# PCB_1c.net
KiCad netlist of a schematic drawn in EAGLE
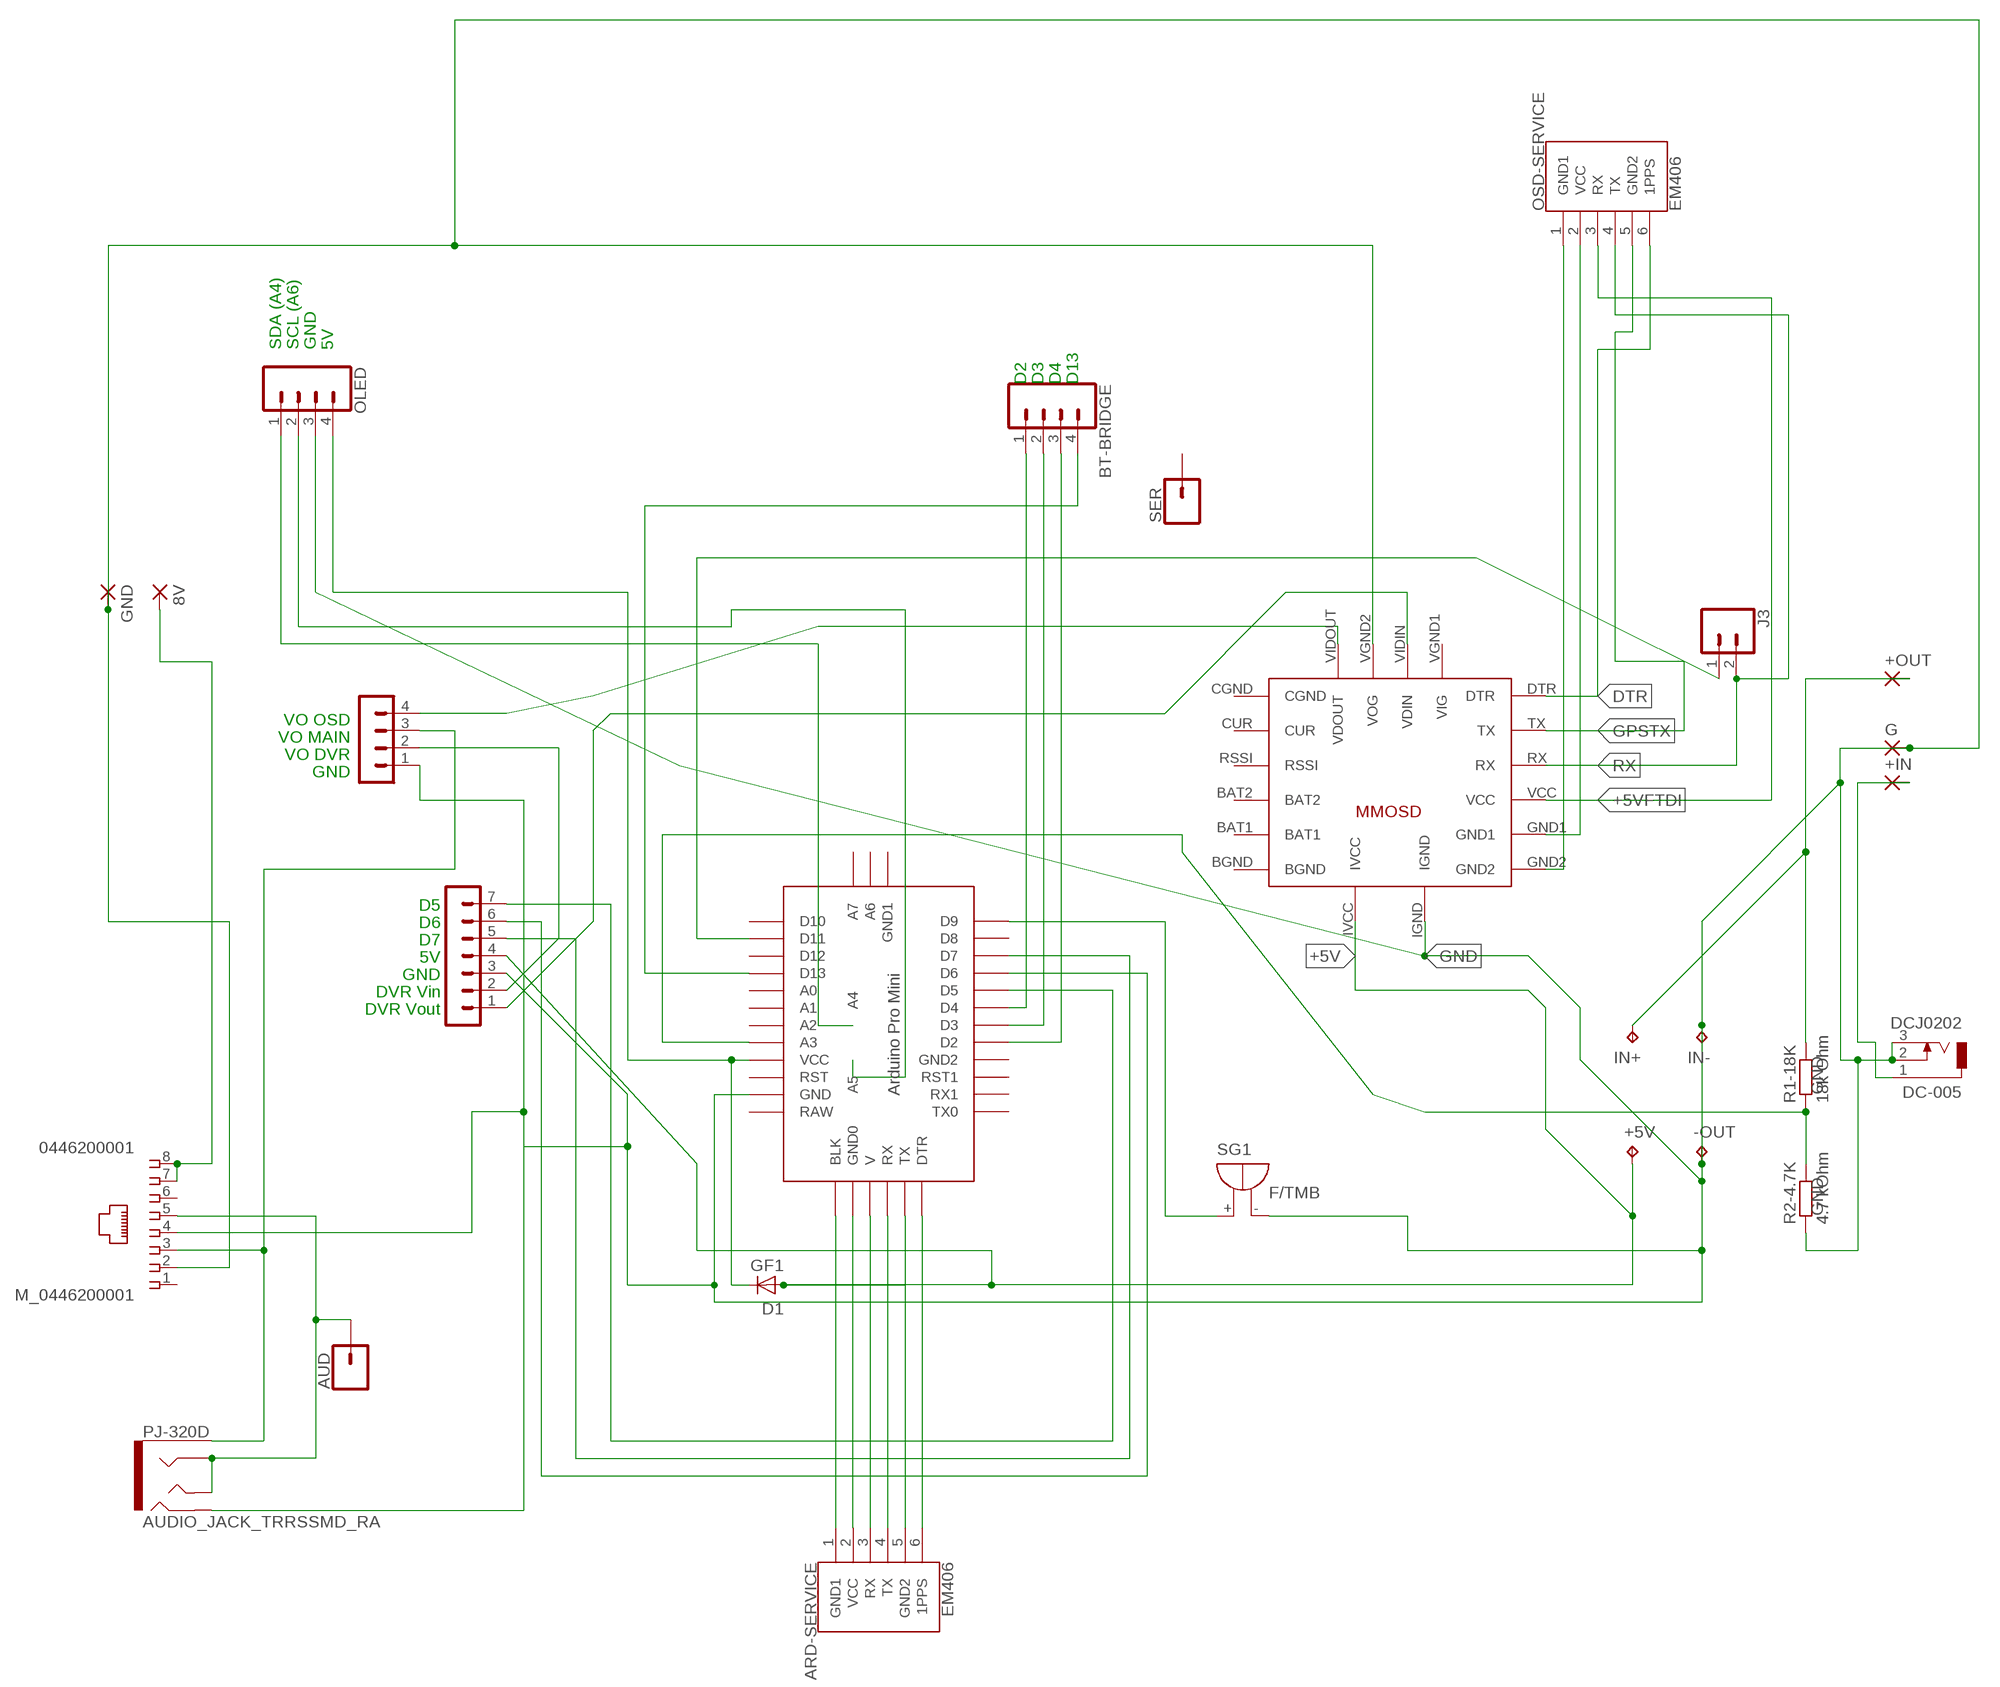
[diagram p0: schematic, sheet 1]

(export (version "E")
  (design (tool "Eeschema 10.0.6"))
  (components
    (comp (ref "+5V")
      (value "TPTP20SQ")
      (footprint "eagle-import:TP20SQ")
      (libsource (lib "eagle-import") (part "TPTP20SQ"))
    )
    (comp (ref "+IN")
      (value "2,54/1,1")
      (footprint "eagle-import:2,54_1,1")
      (libsource (lib "eagle-import") (part "2,54/1,1"))
    )
    (comp (ref "+OUT")
      (value "2,54/1,1")
      (footprint "eagle-import:2,54_1,1")
      (libsource (lib "eagle-import") (part "2,54/1,1"))
    )
    (comp (ref "-OUT")
      (value "TPTP20SQ")
      (footprint "eagle-import:TP20SQ")
      (libsource (lib "eagle-import") (part "TPTP20SQ"))
    )
    (comp (ref "8V")
      (value "2,54/1,1")
      (footprint "eagle-import:2,54_1,1")
      (libsource (lib "eagle-import") (part "2,54/1,1"))
    )
    (comp (ref "ARD-SERVICE")
      (value "EM406")
      (footprint "eagle-import:1X06-1MM")
      (libsource (lib "eagle-import") (part "EM406"))
    )
    (comp (ref "AUD")
      (value "CONN_01")
      (footprint "eagle-import:1X01")
      (libsource (lib "eagle-import") (part "CONN_01"))
    )
    (comp (ref "BT-BRIDGE")
      (value "CONN_04")
      (footprint "eagle-import:1X04")
      (libsource (lib "eagle-import") (part "CONN_04"))
    )
    (comp (ref "D1")
      (value "GF1")
      (footprint "eagle-import:SMA-DO214AC")
      (libsource (lib "eagle-import") (part "GF1"))
    )
    (comp (ref "DC-005")
      (value "DCJ0202")
      (footprint "eagle-import:DCJ0202")
      (libsource (lib "eagle-import") (part "DCJ0202"))
    )
    (comp (ref "DVR/MODULE-IO")
      (value "MA07-1")
      (footprint "eagle-import:MA07-1")
      (libsource (lib "eagle-import") (part "MA07-1"))
    )
    (comp (ref "G")
      (value "2,54/1,1")
      (footprint "eagle-import:2,54_1,1")
      (libsource (lib "eagle-import") (part "2,54/1,1"))
    )
    (comp (ref "GND")
      (value "2,54/1,1")
      (footprint "eagle-import:2,54_1,1")
      (libsource (lib "eagle-import") (part "2,54/1,1"))
    )
    (comp (ref "IN+")
      (value "TPTP20SQ")
      (footprint "eagle-import:TP20SQ")
      (libsource (lib "eagle-import") (part "TPTP20SQ"))
    )
    (comp (ref "IN-")
      (value "TPTP20SQ")
      (footprint "eagle-import:TP20SQ")
      (libsource (lib "eagle-import") (part "TPTP20SQ"))
    )
    (comp (ref "J3")
      (value "CONN_02")
      (footprint "eagle-import:1X02")
      (libsource (lib "eagle-import") (part "CONN_02"))
    )
    (comp (ref "MINIMOSD")
      (value "MICROMINIMOSDPWR")
      (footprint "eagle-import:MMOSDNVDVID")
      (libsource (lib "eagle-import") (part "MICROMINIMOSDPWR"))
    )
    (comp (ref "M_0446200001")
      (value "0446200001")
      (footprint "eagle-import:0446200001")
      (fields (field (name "MF") "MOLEX"))
      (libsource (lib "eagle-import") (part "0446200001"))
    )
    (comp (ref "OLED")
      (value "CONN_04")
      (footprint "eagle-import:1X04")
      (libsource (lib "eagle-import") (part "CONN_04"))
    )
    (comp (ref "OSD-SERVICE")
      (value "EM406")
      (footprint "eagle-import:1X06-1MM")
      (libsource (lib "eagle-import") (part "EM406"))
    )
    (comp (ref "PJ-320D")
      (value "AUDIO_JACK_TRRSSMD_RA")
      (footprint "eagle-import:AUDIO_JACK_3.5MM_TRRS_SMD_RA")
      (libsource (lib "eagle-import") (part "AUDIO_JACK_TRRSSMD_RA"))
    )
    (comp (ref "R1-18K")
      (value "18k Ohm")
      (footprint "eagle-import:M1206")
      (libsource (lib "eagle-import") (part "R-EU_M1206"))
    )
    (comp (ref "R2-4.7K")
      (value "4.7 kOhm")
      (footprint "eagle-import:M1206")
      (libsource (lib "eagle-import") (part "R-EU_M1206"))
    )
    (comp (ref "SER")
      (value "CONN_01")
      (footprint "eagle-import:1X01")
      (libsource (lib "eagle-import") (part "CONN_01"))
    )
    (comp (ref "SG1")
      (value "F/TMB")
      (footprint "eagle-import:F_TMB")
      (libsource (lib "eagle-import") (part "F/TMB"))
    )
    (comp (ref "U$1")
      (value "ABK-PRO-MINI")
      (footprint "eagle-import:ABK-PRO-MINI")
      (libsource (lib "eagle-import") (part "ABK-PRO-MINI"))
    )
    (comp (ref "V-IO")
      (value "MA04-1")
      (footprint "eagle-import:MA04-1")
      (libsource (lib "eagle-import") (part "MA04-1"))
    )
  )
  (nets
    (net (code "1") (name "+5V") (class "Default")
      (node (ref "+5V") (pin "TP") (pinfunction "TP_TP") (pintype "input"))
      (node (ref "D1") (pin "A") (pinfunction "A_A") (pintype "passive"))
      (node (ref "DVR/MODULE-IO") (pin "4") (pinfunction "4_4") (pintype "passive"))
      (node (ref "MINIMOSD") (pin "IVCC") (pinfunction "IVCC_IVCC") (pintype "power_in"))
    )
    (net (code "2") (name "+5VFTDI") (class "Default")
      (node (ref "MINIMOSD") (pin "VCC") (pinfunction "VCC_VCC") (pintype "power_in"))
      (node (ref "OSD-SERVICE") (pin "3") (pinfunction "RX_3") (pintype "bidirectional"))
    )
    (net (code "3") (name "/BAT1") (class "Default")
      (node (ref "MINIMOSD") (pin "BAT1") (pinfunction "BAT1_BAT1") (pintype "power_in"))
    )
    (net (code "4") (name "/BAT2") (class "Default")
      (node (ref "MINIMOSD") (pin "BAT2") (pinfunction "BAT2_BAT2") (pintype "power_in"))
    )
    (net (code "5") (name "/BGND") (class "Default")
      (node (ref "MINIMOSD") (pin "BGND") (pinfunction "BGND_BGND") (pintype "power_in"))
    )
    (net (code "6") (name "/CGND") (class "Default")
      (node (ref "MINIMOSD") (pin "CGND") (pinfunction "CGND_CGND") (pintype "power_in"))
    )
    (net (code "7") (name "DTR") (class "Default")
      (node (ref "MINIMOSD") (pin "DTR") (pinfunction "DTR_DTR") (pintype "bidirectional"))
      (node (ref "OSD-SERVICE") (pin "6") (pinfunction "1PPS_6") (pintype "bidirectional"))
    )
    (net (code "8") (name "GND") (class "Default")
      (node (ref "-OUT") (pin "TP") (pinfunction "TP_TP") (pintype "input"))
      (node (ref "DC-005") (pin "2") (pinfunction "2_2") (pintype "passive"))
      (node (ref "DC-005") (pin "3") (pinfunction "3_3") (pintype "passive"))
      (node (ref "DVR/MODULE-IO") (pin "3") (pinfunction "3_3") (pintype "passive"))
      (node (ref "G") (pin "1") (pinfunction "P_1") (pintype "passive"))
      (node (ref "GND") (pin "1") (pinfunction "P_1") (pintype "passive"))
      (node (ref "IN-") (pin "TP") (pinfunction "TP_TP") (pintype "input"))
      (node (ref "MINIMOSD") (pin "IGND") (pinfunction "IGND_IGND") (pintype "power_in"))
      (node (ref "MINIMOSD") (pin "VGND2") (pinfunction "VOG_VGND2") (pintype "output"))
      (node (ref "M_0446200001") (pin "2") (pinfunction "2_2") (pintype "passive"))
      (node (ref "M_0446200001") (pin "4") (pinfunction "4_4") (pintype "passive"))
      (node (ref "OLED") (pin "3") (pinfunction "3_3") (pintype "passive"))
      (node (ref "PJ-320D") (pin "RING2") (pinfunction "RING2_RING2") (pintype "bidirectional"))
      (node (ref "R2-4.7K") (pin "1") (pinfunction "1_1") (pintype "passive"))
      (node (ref "SG1") (pin "-") (pinfunction "-_-") (pintype "passive"))
      (node (ref "U$1") (pin "GND") (pinfunction "GND_GND") (pintype "bidirectional"))
      (node (ref "V-IO") (pin "1") (pinfunction "1_1") (pintype "passive"))
    )
    (net (code "9") (name "GPSTX") (class "Default")
      (node (ref "MINIMOSD") (pin "TX") (pinfunction "TX_TX") (pintype "output"))
      (node (ref "OSD-SERVICE") (pin "5") (pinfunction "GND2_5") (pintype "bidirectional"))
    )
    (net (code "10") (name "Net-(+IN-P)") (class "Default")
      (node (ref "+IN") (pin "1") (pinfunction "P_1") (pintype "passive"))
      (node (ref "DC-005") (pin "1") (pinfunction "1_1") (pintype "passive"))
    )
    (net (code "11") (name "Net-(+OUT-P)") (class "Default")
      (node (ref "+OUT") (pin "1") (pinfunction "P_1") (pintype "passive"))
      (node (ref "IN+") (pin "TP") (pinfunction "TP_TP") (pintype "input"))
      (node (ref "R1-18K") (pin "2") (pinfunction "2_2") (pintype "passive"))
    )
    (net (code "12") (name "Net-(8V-P)") (class "Default")
      (node (ref "8V") (pin "1") (pinfunction "P_1") (pintype "passive"))
      (node (ref "M_0446200001") (pin "7") (pinfunction "7_7") (pintype "passive"))
      (node (ref "M_0446200001") (pin "8") (pinfunction "8_8") (pintype "passive"))
    )
    (net (code "13") (name "Net-(ARD-SERVICE-1PPS)") (class "Default")
      (node (ref "ARD-SERVICE") (pin "6") (pinfunction "1PPS_6") (pintype "bidirectional"))
      (node (ref "U$1") (pin "DTR") (pinfunction "DTR_DTR") (pintype "bidirectional"))
    )
    (net (code "14") (name "Net-(ARD-SERVICE-GND1)") (class "Default")
      (node (ref "ARD-SERVICE") (pin "1") (pinfunction "GND1_1") (pintype "bidirectional"))
      (node (ref "U$1") (pin "BLK") (pinfunction "BLK_BLK") (pintype "bidirectional"))
    )
    (net (code "15") (name "Net-(ARD-SERVICE-GND2)") (class "Default")
      (node (ref "ARD-SERVICE") (pin "5") (pinfunction "GND2_5") (pintype "bidirectional"))
      (node (ref "U$1") (pin "TX01") (pinfunction "TX_TX01") (pintype "bidirectional"))
    )
    (net (code "16") (name "Net-(ARD-SERVICE-RX)") (class "Default")
      (node (ref "ARD-SERVICE") (pin "3") (pinfunction "RX_3") (pintype "bidirectional"))
      (node (ref "U$1") (pin "5V") (pinfunction "V_5V") (pintype "bidirectional"))
    )
    (net (code "17") (name "Net-(ARD-SERVICE-TX)") (class "Default")
      (node (ref "ARD-SERVICE") (pin "4") (pinfunction "TX_4") (pintype "bidirectional"))
      (node (ref "U$1") (pin "RX01") (pinfunction "RX_RX01") (pintype "bidirectional"))
    )
    (net (code "18") (name "Net-(ARD-SERVICE-VCC)") (class "Default")
      (node (ref "ARD-SERVICE") (pin "2") (pinfunction "VCC_2") (pintype "bidirectional"))
      (node (ref "U$1") (pin "G") (pinfunction "GND0_G") (pintype "bidirectional"))
    )
    (net (code "19") (name "Net-(AUD-Pad1)") (class "Default")
      (node (ref "AUD") (pin "1") (pinfunction "1_1") (pintype "passive"))
      (node (ref "M_0446200001") (pin "5") (pinfunction "5_5") (pintype "passive"))
      (node (ref "PJ-320D") (pin "RING1") (pinfunction "RING1_RING1") (pintype "bidirectional"))
      (node (ref "PJ-320D") (pin "TIP") (pinfunction "TIP_TIP") (pintype "bidirectional"))
    )
    (net (code "20") (name "Net-(BT-BRIDGE-Pad1)") (class "Default")
      (node (ref "BT-BRIDGE") (pin "1") (pinfunction "1_1") (pintype "passive"))
      (node (ref "U$1") (pin "D4") (pinfunction "D4_D4") (pintype "bidirectional"))
    )
    (net (code "21") (name "Net-(BT-BRIDGE-Pad2)") (class "Default")
      (node (ref "BT-BRIDGE") (pin "2") (pinfunction "2_2") (pintype "passive"))
      (node (ref "U$1") (pin "D3") (pinfunction "D3_D3") (pintype "bidirectional"))
    )
    (net (code "22") (name "Net-(BT-BRIDGE-Pad3)") (class "Default")
      (node (ref "BT-BRIDGE") (pin "3") (pinfunction "3_3") (pintype "passive"))
      (node (ref "U$1") (pin "D2") (pinfunction "D2_D2") (pintype "bidirectional"))
    )
    (net (code "23") (name "Net-(BT-BRIDGE-Pad4)") (class "Default")
      (node (ref "BT-BRIDGE") (pin "4") (pinfunction "4_4") (pintype "passive"))
      (node (ref "U$1") (pin "D13") (pinfunction "D13_D13") (pintype "bidirectional"))
    )
    (net (code "24") (name "Net-(D1-C)") (class "Default")
      (node (ref "D1") (pin "K") (pinfunction "C_K") (pintype "passive"))
      (node (ref "OLED") (pin "4") (pinfunction "4_4") (pintype "passive"))
      (node (ref "U$1") (pin "VCC") (pinfunction "VCC_VCC") (pintype "bidirectional"))
    )
    (net (code "25") (name "Net-(DVR/MODULE-IO-Pad2)") (class "Default")
      (node (ref "DVR/MODULE-IO") (pin "2") (pinfunction "2_2") (pintype "passive"))
      (node (ref "V-IO") (pin "2") (pinfunction "2_2") (pintype "passive"))
    )
    (net (code "26") (name "Net-(DVR/MODULE-IO-Pad5)") (class "Default")
      (node (ref "DVR/MODULE-IO") (pin "5") (pinfunction "5_5") (pintype "passive"))
      (node (ref "U$1") (pin "D7") (pinfunction "D7_D7") (pintype "bidirectional"))
    )
    (net (code "27") (name "Net-(DVR/MODULE-IO-Pad6)") (class "Default")
      (node (ref "DVR/MODULE-IO") (pin "6") (pinfunction "6_6") (pintype "passive"))
      (node (ref "U$1") (pin "D6") (pinfunction "D6_D6") (pintype "bidirectional"))
    )
    (net (code "28") (name "Net-(DVR/MODULE-IO-Pad7)") (class "Default")
      (node (ref "DVR/MODULE-IO") (pin "7") (pinfunction "7_7") (pintype "passive"))
      (node (ref "U$1") (pin "D5") (pinfunction "D5_D5") (pintype "bidirectional"))
    )
    (net (code "29") (name "Net-(J3-Pad1)") (class "Default")
      (node (ref "J3") (pin "1") (pinfunction "1_1") (pintype "passive"))
      (node (ref "U$1") (pin "D11") (pinfunction "D11_D11") (pintype "bidirectional"))
    )
    (net (code "30") (name "Net-(MINIMOSD-VDIN)") (class "Default")
      (node (ref "DVR/MODULE-IO") (pin "1") (pinfunction "1_1") (pintype "passive"))
      (node (ref "MINIMOSD") (pin "VIDIN") (pinfunction "VDIN_VIDIN") (pintype "input"))
    )
    (net (code "31") (name "Net-(MINIMOSD-VDOUT)") (class "Default")
      (node (ref "MINIMOSD") (pin "VIDOUT") (pinfunction "VDOUT_VIDOUT") (pintype "output"))
      (node (ref "V-IO") (pin "4") (pinfunction "4_4") (pintype "passive"))
    )
    (net (code "32") (name "Net-(M_0446200001-Pad3)") (class "Default")
      (node (ref "M_0446200001") (pin "3") (pinfunction "3_3") (pintype "passive"))
      (node (ref "PJ-320D") (pin "EARTH") (pinfunction "EARTH_EARTH") (pintype "bidirectional"))
      (node (ref "V-IO") (pin "3") (pinfunction "3_3") (pintype "passive"))
    )
    (net (code "33") (name "Net-(OLED-Pad1)") (class "Default")
      (node (ref "OLED") (pin "1") (pinfunction "1_1") (pintype "passive"))
      (node (ref "U$1") (pin "A4") (pinfunction "A4_A4") (pintype "bidirectional"))
    )
    (net (code "34") (name "Net-(OLED-Pad2)") (class "Default")
      (node (ref "OLED") (pin "2") (pinfunction "2_2") (pintype "passive"))
      (node (ref "U$1") (pin "A5") (pinfunction "A5_A5") (pintype "bidirectional"))
    )
    (net (code "35") (name "Net-(OSD-SERVICE-GND1)") (class "Default")
      (node (ref "MINIMOSD") (pin "GND2") (pinfunction "GND2_GND2") (pintype "power_in"))
      (node (ref "OSD-SERVICE") (pin "1") (pinfunction "GND1_1") (pintype "bidirectional"))
    )
    (net (code "36") (name "Net-(OSD-SERVICE-VCC)") (class "Default")
      (node (ref "MINIMOSD") (pin "GND1") (pinfunction "GND1_GND1") (pintype "power_in"))
      (node (ref "OSD-SERVICE") (pin "2") (pinfunction "VCC_2") (pintype "bidirectional"))
    )
    (net (code "37") (name "Net-(SG1-Pad+)") (class "Default")
      (node (ref "SG1") (pin "+") (pinfunction "+_+") (pintype "passive"))
      (node (ref "U$1") (pin "D9") (pinfunction "D9_D9") (pintype "bidirectional"))
    )
    (net (code "38") (name "Net-(U$1-A3)") (class "Default")
      (node (ref "R1-18K") (pin "1") (pinfunction "1_1") (pintype "passive"))
      (node (ref "R2-4.7K") (pin "2") (pinfunction "2_2") (pintype "passive"))
      (node (ref "U$1") (pin "A0") (pinfunction "A3_A0") (pintype "bidirectional"))
    )
    (net (code "39") (name "RX") (class "Default")
      (node (ref "J3") (pin "2") (pinfunction "2_2") (pintype "passive"))
      (node (ref "MINIMOSD") (pin "RX") (pinfunction "RX_RX") (pintype "input"))
      (node (ref "OSD-SERVICE") (pin "4") (pinfunction "TX_4") (pintype "bidirectional"))
    )
    (net (code "40") (name "unconnected-(MINIMOSD-PadCUR)") (class "Default")
      (node (ref "MINIMOSD") (pin "CUR") (pinfunction "CUR_CUR") (pintype "bidirectional"))
    )
    (net (code "41") (name "unconnected-(MINIMOSD-PadRSSI)") (class "Default")
      (node (ref "MINIMOSD") (pin "RSSI") (pinfunction "RSSI_RSSI") (pintype "bidirectional"))
    )
    (net (code "42") (name "unconnected-(MINIMOSD-VIG-PadVGND1)") (class "Default")
      (node (ref "MINIMOSD") (pin "VGND1") (pinfunction "VIG_VGND1") (pintype "input"))
    )
    (net (code "43") (name "unconnected-(M_0446200001-Pad1)") (class "Default")
      (node (ref "M_0446200001") (pin "1") (pinfunction "1_1") (pintype "passive"))
    )
    (net (code "44") (name "unconnected-(M_0446200001-Pad6)") (class "Default")
      (node (ref "M_0446200001") (pin "6") (pinfunction "6_6") (pintype "passive"))
    )
    (net (code "45") (name "unconnected-(SER-Pad1)") (class "Default")
      (node (ref "SER") (pin "1") (pinfunction "1_1") (pintype "passive"))
    )
    (net (code "46") (name "unconnected-(U$1-A0-PadA3)") (class "Default")
      (node (ref "U$1") (pin "A3") (pinfunction "A0_A3") (pintype "bidirectional"))
    )
    (net (code "47") (name "unconnected-(U$1-A1-PadA2)") (class "Default")
      (node (ref "U$1") (pin "A2") (pinfunction "A1_A2") (pintype "bidirectional"))
    )
    (net (code "48") (name "unconnected-(U$1-A2-PadA1)") (class "Default")
      (node (ref "U$1") (pin "A1") (pinfunction "A2_A1") (pintype "bidirectional"))
    )
    (net (code "49") (name "unconnected-(U$1-GND1-PadGND4)") (class "Default")
      (node (ref "U$1") (pin "GND4") (pinfunction "GND1_GND4") (pintype "bidirectional"))
    )
    (net (code "50") (name "unconnected-(U$1-GND2-PadGND1)") (class "Default")
      (node (ref "U$1") (pin "GND1") (pinfunction "GND2_GND1") (pintype "bidirectional"))
    )
    (net (code "51") (name "unconnected-(U$1-PadA6)") (class "Default")
      (node (ref "U$1") (pin "A6") (pinfunction "A6_A6") (pintype "bidirectional"))
    )
    (net (code "52") (name "unconnected-(U$1-PadA7)") (class "Default")
      (node (ref "U$1") (pin "A7") (pinfunction "A7_A7") (pintype "bidirectional"))
    )
    (net (code "53") (name "unconnected-(U$1-PadD8)") (class "Default")
      (node (ref "U$1") (pin "D8") (pinfunction "D8_D8") (pintype "bidirectional"))
    )
    (net (code "54") (name "unconnected-(U$1-PadD10)") (class "Default")
      (node (ref "U$1") (pin "D10") (pinfunction "D10_D10") (pintype "bidirectional"))
    )
    (net (code "55") (name "unconnected-(U$1-PadD12)") (class "Default")
      (node (ref "U$1") (pin "D12") (pinfunction "D12_D12") (pintype "bidirectional"))
    )
    (net (code "56") (name "unconnected-(U$1-PadRAW)") (class "Default")
      (node (ref "U$1") (pin "RAW") (pinfunction "RAW_RAW") (pintype "bidirectional"))
    )
    (net (code "57") (name "unconnected-(U$1-PadRST)") (class "Default")
      (node (ref "U$1") (pin "RST") (pinfunction "RST_RST") (pintype "bidirectional"))
    )
    (net (code "58") (name "unconnected-(U$1-PadRST1)") (class "Default")
      (node (ref "U$1") (pin "RST1") (pinfunction "RST1_RST1") (pintype "bidirectional"))
    )
    (net (code "59") (name "unconnected-(U$1-PadRX1)") (class "Default")
      (node (ref "U$1") (pin "RX1") (pinfunction "RX1_RX1") (pintype "bidirectional"))
    )
    (net (code "60") (name "unconnected-(U$1-PadTX0)") (class "Default")
      (node (ref "U$1") (pin "TX0") (pinfunction "TX0_TX0") (pintype "bidirectional"))
    )
  )
)
